# vista_air_beta_1.net
KiCad netlist of a schematic drawn in EAGLE
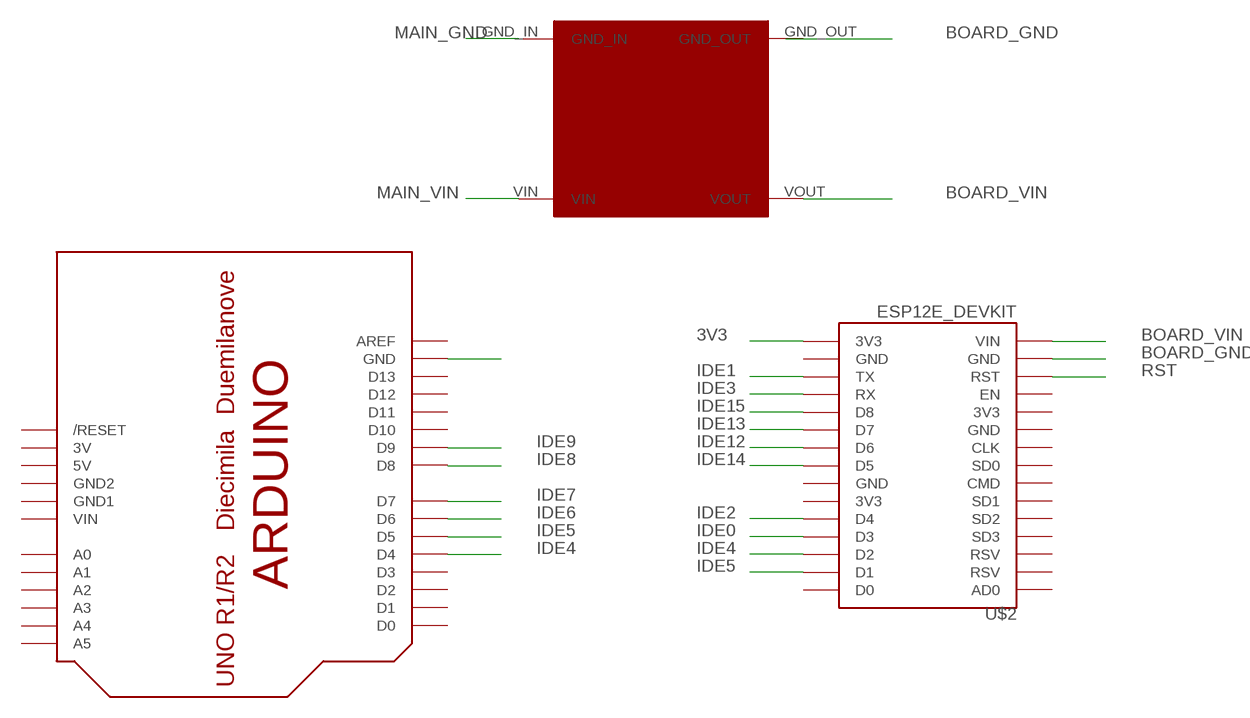
[diagram p0: schematic, sheet 1]

(export (version "E")
  (design (tool "Eeschema 10.0.6"))
  (components
    (comp (ref "U$1")
      (value "ARDUINOUNO")
      (footprint "eagle-import:ARDUINO")
      (libsource (lib "eagle-import") (part "ARDUINOUNO"))
    )
    (comp (ref "U$2")
      (value "ESP12E_DEVKIT")
      (footprint "eagle-import:ESP12E_DEVKIT")
      (libsource (lib "eagle-import") (part "ESP12E_DEVKIT"))
    )
    (comp (ref "U$3")
      (value "MP1584EN_STEPDOWN_MODULE")
      (footprint "eagle-import:MP1584EN_STEPDOWN_MODULE")
      (libsource (lib "eagle-import") (part "MP1584EN_STEPDOWN_MODULE"))
    )
  )
  (nets
    (net (code "1") (name "/3V") (class "Default")
      (node (ref "U$1") (pin "3V") (pinfunction "3V_3V") (pintype "power_in"))
    )
    (net (code "2") (name "/3V3") (class "Default")
      (node (ref "U$2") (pin "3V3@2") (pinfunction "3V3_3V3@2") (pintype "bidirectional"))
    )
    (net (code "3") (name "/5V") (class "Default")
      (node (ref "U$1") (pin "5V") (pinfunction "5V_5V") (pintype "power_in"))
    )
    (net (code "4") (name "/BOARD_GND") (class "Default")
      (node (ref "U$1") (pin "GND") (pinfunction "GND_GND") (pintype "power_in"))
      (node (ref "U$2") (pin "GND@1") (pinfunction "GND_GND@1") (pintype "bidirectional"))
    )
    (net (code "5") (name "/BOARD_VIN") (class "Default")
      (node (ref "U$2") (pin "VIN") (pinfunction "VIN_VIN") (pintype "bidirectional"))
      (node (ref "U$3") (pin "VOUT") (pinfunction "VOUT_VOUT") (pintype "bidirectional"))
    )
    (net (code "6") (name "/GND1") (class "Default")
      (node (ref "U$1") (pin "GND1") (pinfunction "GND1_GND1") (pintype "power_in"))
    )
    (net (code "7") (name "/GND2") (class "Default")
      (node (ref "U$1") (pin "GND2") (pinfunction "GND2_GND2") (pintype "power_in"))
    )
    (net (code "8") (name "/IDE0") (class "Default")
      (node (ref "U$2") (pin "D3") (pinfunction "D3_D3") (pintype "bidirectional"))
    )
    (net (code "9") (name "/IDE1") (class "Default")
      (node (ref "U$2") (pin "TX") (pinfunction "TX_TX") (pintype "bidirectional"))
    )
    (net (code "10") (name "/IDE2") (class "Default")
      (node (ref "U$2") (pin "D4") (pinfunction "D4_D4") (pintype "bidirectional"))
    )
    (net (code "11") (name "/IDE3") (class "Default")
      (node (ref "U$2") (pin "RX") (pinfunction "RX_RX") (pintype "bidirectional"))
    )
    (net (code "12") (name "/IDE4") (class "Default")
      (node (ref "U$1") (pin "D4") (pinfunction "D4_D4") (pintype "bidirectional"))
      (node (ref "U$2") (pin "D2") (pinfunction "D2_D2") (pintype "bidirectional"))
    )
    (net (code "13") (name "/IDE5") (class "Default")
      (node (ref "U$1") (pin "D5") (pinfunction "D5_D5") (pintype "bidirectional"))
      (node (ref "U$2") (pin "D1") (pinfunction "D1_D1") (pintype "bidirectional"))
    )
    (net (code "14") (name "/IDE6") (class "Default")
      (node (ref "U$1") (pin "D6") (pinfunction "D6_D6") (pintype "bidirectional"))
    )
    (net (code "15") (name "/IDE7") (class "Default")
      (node (ref "U$1") (pin "D7") (pinfunction "D7_D7") (pintype "bidirectional"))
    )
    (net (code "16") (name "/IDE8") (class "Default")
      (node (ref "U$1") (pin "D8") (pinfunction "D8_D8") (pintype "bidirectional"))
    )
    (net (code "17") (name "/IDE9") (class "Default")
      (node (ref "U$1") (pin "D9") (pinfunction "D9_D9") (pintype "bidirectional"))
    )
    (net (code "18") (name "/IDE12") (class "Default")
      (node (ref "U$2") (pin "D6") (pinfunction "D6_D6") (pintype "bidirectional"))
    )
    (net (code "19") (name "/IDE13") (class "Default")
      (node (ref "U$2") (pin "D7") (pinfunction "D7_D7") (pintype "bidirectional"))
    )
    (net (code "20") (name "/IDE14") (class "Default")
      (node (ref "U$2") (pin "D5") (pinfunction "D5_D5") (pintype "bidirectional"))
    )
    (net (code "21") (name "/IDE15") (class "Default")
      (node (ref "U$2") (pin "D8") (pinfunction "D8_D8") (pintype "bidirectional"))
    )
    (net (code "22") (name "/MAIN_GND") (class "Default")
      (node (ref "U$3") (pin "GND_IN") (pinfunction "GND_IN_GND_IN") (pintype "bidirectional"))
    )
    (net (code "23") (name "/MAIN_VIN") (class "Default")
      (node (ref "U$3") (pin "VIN") (pinfunction "VIN_VIN") (pintype "bidirectional"))
    )
    (net (code "24") (name "/RST") (class "Default")
      (node (ref "U$2") (pin "RST") (pinfunction "RST_RST") (pintype "bidirectional"))
    )
    (net (code "25") (name "/VIN") (class "Default")
      (node (ref "U$1") (pin "VIN") (pinfunction "VIN_VIN") (pintype "power_in"))
    )
    (net (code "26") (name "unconnected-(U$1-PadA0)") (class "Default")
      (node (ref "U$1") (pin "A0") (pinfunction "A0_A0") (pintype "bidirectional"))
    )
    (net (code "27") (name "unconnected-(U$1-PadA1)") (class "Default")
      (node (ref "U$1") (pin "A1") (pinfunction "A1_A1") (pintype "bidirectional"))
    )
    (net (code "28") (name "unconnected-(U$1-PadA2)") (class "Default")
      (node (ref "U$1") (pin "A2") (pinfunction "A2_A2") (pintype "bidirectional"))
    )
    (net (code "29") (name "unconnected-(U$1-PadA3)") (class "Default")
      (node (ref "U$1") (pin "A3") (pinfunction "A3_A3") (pintype "bidirectional"))
    )
    (net (code "30") (name "unconnected-(U$1-PadA4)") (class "Default")
      (node (ref "U$1") (pin "A4") (pinfunction "A4_A4") (pintype "bidirectional"))
    )
    (net (code "31") (name "unconnected-(U$1-PadA5)") (class "Default")
      (node (ref "U$1") (pin "A5") (pinfunction "A5_A5") (pintype "bidirectional"))
    )
    (net (code "32") (name "unconnected-(U$1-PadAREF)") (class "Default")
      (node (ref "U$1") (pin "AREF") (pinfunction "AREF_AREF") (pintype "bidirectional"))
    )
    (net (code "33") (name "unconnected-(U$1-PadD0)") (class "Default")
      (node (ref "U$1") (pin "D0") (pinfunction "D0_D0") (pintype "bidirectional"))
    )
    (net (code "34") (name "unconnected-(U$1-PadD1)") (class "Default")
      (node (ref "U$1") (pin "D1") (pinfunction "D1_D1") (pintype "bidirectional"))
    )
    (net (code "35") (name "unconnected-(U$1-PadD2)") (class "Default")
      (node (ref "U$1") (pin "D2") (pinfunction "D2_D2") (pintype "bidirectional"))
    )
    (net (code "36") (name "unconnected-(U$1-PadD3)") (class "Default")
      (node (ref "U$1") (pin "D3") (pinfunction "D3_D3") (pintype "bidirectional"))
    )
    (net (code "37") (name "unconnected-(U$1-PadD10)") (class "Default")
      (node (ref "U$1") (pin "D10") (pinfunction "D10_D10") (pintype "bidirectional"))
    )
    (net (code "38") (name "unconnected-(U$1-PadD11)") (class "Default")
      (node (ref "U$1") (pin "D11") (pinfunction "D11_D11") (pintype "bidirectional"))
    )
    (net (code "39") (name "unconnected-(U$1-PadD12)") (class "Default")
      (node (ref "U$1") (pin "D12") (pinfunction "D12_D12") (pintype "bidirectional"))
    )
    (net (code "40") (name "unconnected-(U$1-PadD13)") (class "Default")
      (node (ref "U$1") (pin "D13") (pinfunction "D13_D13") (pintype "bidirectional"))
    )
    (net (code "41") (name "unconnected-(U$1-{slash}RESET-PadRESET)") (class "Default")
      (node (ref "U$1") (pin "RESET") (pinfunction "/RESET_RESET") (pintype "bidirectional"))
    )
    (net (code "42") (name "unconnected-(U$2-3V3-Pad3V3@0)") (class "Default")
      (node (ref "U$2") (pin "3V3@0") (pinfunction "3V3_3V3@0") (pintype "bidirectional"))
    )
    (net (code "43") (name "unconnected-(U$2-3V3-Pad3V3@1)") (class "Default")
      (node (ref "U$2") (pin "3V3@1") (pinfunction "3V3_3V3@1") (pintype "bidirectional"))
    )
    (net (code "44") (name "unconnected-(U$2-GND-PadGND@0)") (class "Default")
      (node (ref "U$2") (pin "GND@0") (pinfunction "GND_GND@0") (pintype "bidirectional"))
    )
    (net (code "45") (name "unconnected-(U$2-GND-PadGND@2)") (class "Default")
      (node (ref "U$2") (pin "GND@2") (pinfunction "GND_GND@2") (pintype "bidirectional"))
    )
    (net (code "46") (name "unconnected-(U$2-GND-PadGND@3)") (class "Default")
      (node (ref "U$2") (pin "GND@3") (pinfunction "GND_GND@3") (pintype "bidirectional"))
    )
    (net (code "47") (name "unconnected-(U$2-PadAD0)") (class "Default")
      (node (ref "U$2") (pin "AD0") (pinfunction "AD0_AD0") (pintype "bidirectional"))
    )
    (net (code "48") (name "unconnected-(U$2-PadCLK)") (class "Default")
      (node (ref "U$2") (pin "CLK") (pinfunction "CLK_CLK") (pintype "bidirectional"))
    )
    (net (code "49") (name "unconnected-(U$2-PadCMD)") (class "Default")
      (node (ref "U$2") (pin "CMD") (pinfunction "CMD_CMD") (pintype "bidirectional"))
    )
    (net (code "50") (name "unconnected-(U$2-PadD0)") (class "Default")
      (node (ref "U$2") (pin "D0") (pinfunction "D0_D0") (pintype "bidirectional"))
    )
    (net (code "51") (name "unconnected-(U$2-PadEN)") (class "Default")
      (node (ref "U$2") (pin "EN") (pinfunction "EN_EN") (pintype "bidirectional"))
    )
    (net (code "52") (name "unconnected-(U$2-PadSD0)") (class "Default")
      (node (ref "U$2") (pin "SD0") (pinfunction "SD0_SD0") (pintype "bidirectional"))
    )
    (net (code "53") (name "unconnected-(U$2-PadSD1)") (class "Default")
      (node (ref "U$2") (pin "SD1") (pinfunction "SD1_SD1") (pintype "bidirectional"))
    )
    (net (code "54") (name "unconnected-(U$2-PadSD2)") (class "Default")
      (node (ref "U$2") (pin "SD2") (pinfunction "SD2_SD2") (pintype "bidirectional"))
    )
    (net (code "55") (name "unconnected-(U$2-PadSD3)") (class "Default")
      (node (ref "U$2") (pin "SD3") (pinfunction "SD3_SD3") (pintype "bidirectional"))
    )
    (net (code "56") (name "unconnected-(U$2-RSV-PadRSV@0)") (class "Default")
      (node (ref "U$2") (pin "RSV@0") (pinfunction "RSV_RSV@0") (pintype "bidirectional"))
    )
    (net (code "57") (name "unconnected-(U$2-RSV-PadRSV@1)") (class "Default")
      (node (ref "U$2") (pin "RSV@1") (pinfunction "RSV_RSV@1") (pintype "bidirectional"))
    )
    (net (code "58") (name "unconnected-(U$3-PadGND_OUT)") (class "Default")
      (node (ref "U$3") (pin "GND_OUT") (pinfunction "GND_OUT_GND_OUT") (pintype "bidirectional"))
    )
  )
)
